# ESP-LED-Schematic.net
KiCad netlist of a schematic drawn in Altium Designer
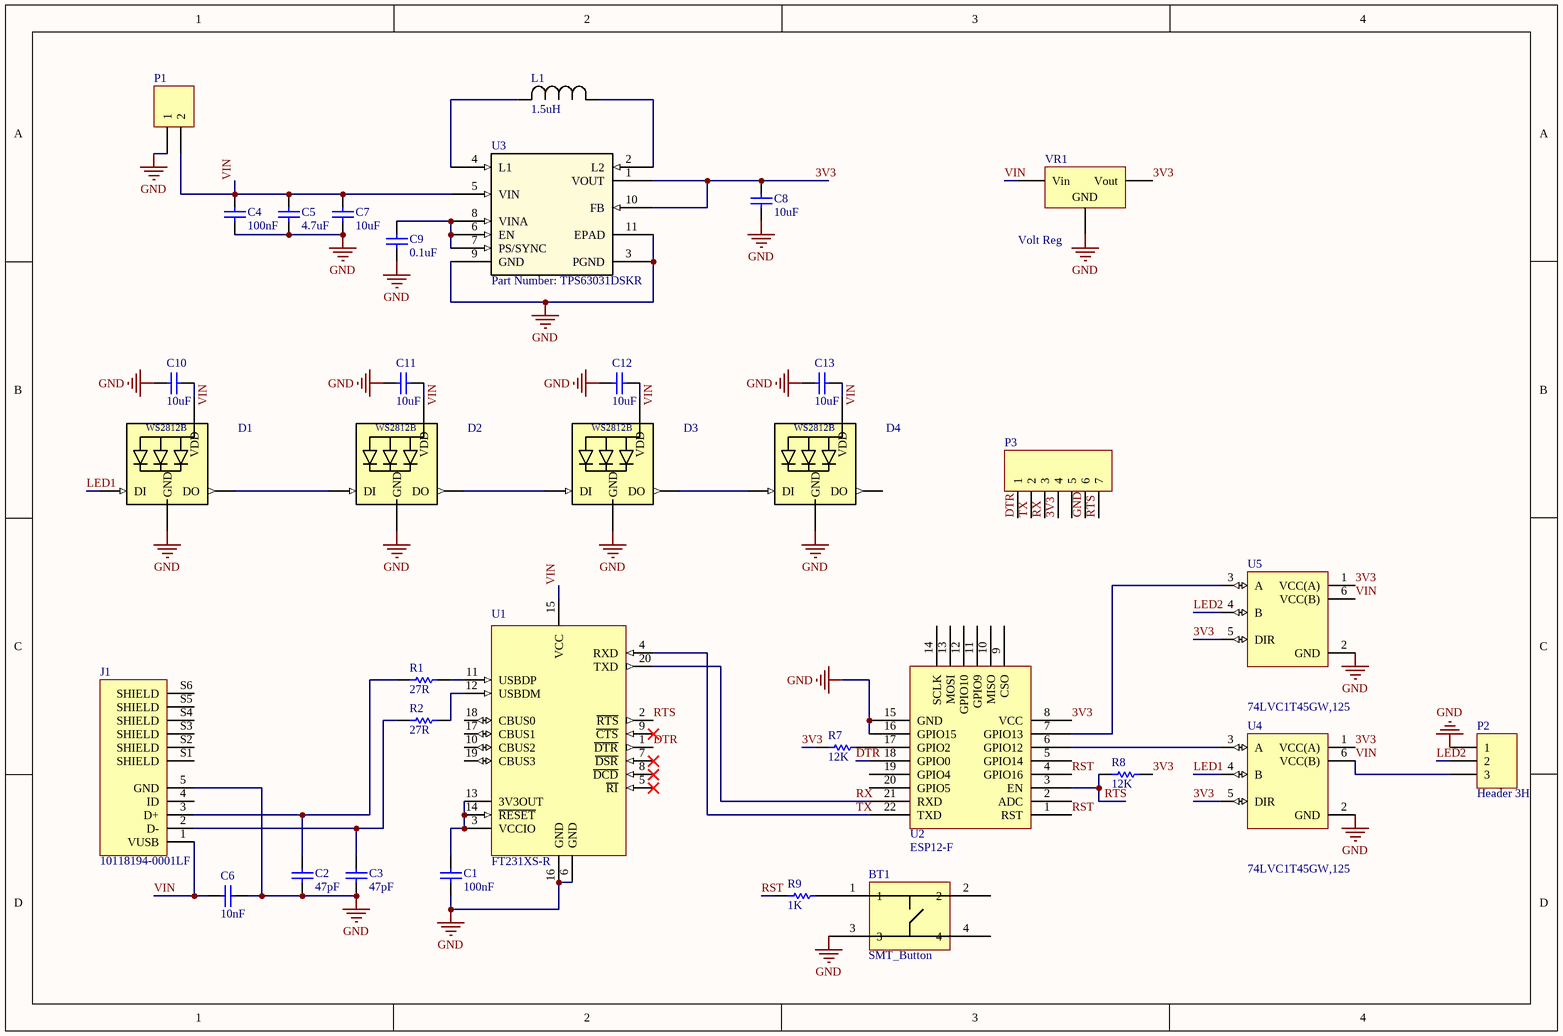
[diagram p0: ESP-LED-Schematic.SchDoc]

(export (version "E")
  (design (tool "Eeschema 10.0.6"))
  (components
    (comp (ref "BT1")
      (value "SMT_Button")
      (footprint "SMT_Button")
      (libsource (lib "CustomComponentsLibrary") (part "SMT_Button"))
    )
    (comp (ref "C1")
      (value "100nF")
      (footprint "6-0805_M")
      (description "Capacitor")
      (fields (field (name "PUBLISHER") "Altium Limited"))
      (libsource (lib "Miscellaneous Devices") (part "Cap"))
    )
    (comp (ref "C2")
      (value "47pF")
      (footprint "6-0805_M")
      (description "Capacitor")
      (fields (field (name "PUBLISHER") "Altium Limited"))
      (libsource (lib "Miscellaneous Devices") (part "Cap"))
    )
    (comp (ref "C3")
      (value "47pF")
      (footprint "6-0805_M")
      (description "Capacitor")
      (fields (field (name "PUBLISHER") "Altium Limited"))
      (libsource (lib "Miscellaneous Devices") (part "Cap"))
    )
    (comp (ref "C4")
      (value "100nF")
      (footprint "6-0805_M")
      (description "Capacitor")
      (fields (field (name "PUBLISHER") "Altium Limited"))
      (libsource (lib "Miscellaneous Devices") (part "Cap"))
    )
    (comp (ref "C5")
      (value "4.7uF")
      (footprint "6-0805_M")
      (description "Capacitor")
      (fields (field (name "PUBLISHER") "Altium Limited"))
      (libsource (lib "Miscellaneous Devices") (part "Cap"))
    )
    (comp (ref "C6")
      (value "10nF")
      (footprint "6-0805_M")
      (description "Capacitor")
      (fields (field (name "PUBLISHER") "Altium Limited"))
      (libsource (lib "Miscellaneous Devices") (part "Cap"))
    )
    (comp (ref "C7")
      (value "10uF")
      (footprint "6-0805_M")
      (description "Capacitor")
      (fields (field (name "PUBLISHER") "Altium Limited"))
      (libsource (lib "Miscellaneous Devices") (part "Cap"))
    )
    (comp (ref "C8")
      (value "10uF")
      (footprint "6-0805_M")
      (description "Capacitor")
      (fields (field (name "PUBLISHER") "Altium Limited"))
      (libsource (lib "Miscellaneous Devices") (part "Cap"))
    )
    (comp (ref "C9")
      (value "0.1uF")
      (footprint "6-0805_M")
      (description "Capacitor")
      (fields (field (name "PUBLISHER") "Altium Limited"))
      (libsource (lib "Miscellaneous Devices") (part "Cap"))
    )
    (comp (ref "C10")
      (value "10uF")
      (footprint "6-0805_M")
      (description "Capacitor")
      (fields (field (name "PUBLISHER") "Altium Limited"))
      (libsource (lib "Miscellaneous Devices") (part "Cap"))
    )
    (comp (ref "C11")
      (value "10uF")
      (footprint "6-0805_M")
      (description "Capacitor")
      (fields (field (name "PUBLISHER") "Altium Limited"))
      (libsource (lib "Miscellaneous Devices") (part "Cap"))
    )
    (comp (ref "C12")
      (value "10uF")
      (footprint "6-0805_M")
      (description "Capacitor")
      (fields (field (name "PUBLISHER") "Altium Limited"))
      (libsource (lib "Miscellaneous Devices") (part "Cap"))
    )
    (comp (ref "C13")
      (value "10uF")
      (footprint "6-0805_M")
      (description "Capacitor")
      (fields (field (name "PUBLISHER") "Altium Limited"))
      (libsource (lib "Miscellaneous Devices") (part "Cap"))
    )
    (comp (ref "D1")
      (value "WS2812B")
      (footprint "*WS2812B_WS2812B(Primary)")
      (description "Intelligent Control Led Integrated Light Source Pack Of 10")
      (fields (field (name "MF") "Worldsemi") (field (name "DIGI-KEY_PART_NUMBER") "1597-1565-ND"))
      (libsource (lib "WS2812B") (part "WS2812B"))
    )
    (comp (ref "D2")
      (value "WS2812B")
      (footprint "*WS2812B_WS2812B(Primary)")
      (description "Intelligent Control Led Integrated Light Source Pack Of 10")
      (fields (field (name "MF") "Worldsemi") (field (name "DIGI-KEY_PART_NUMBER") "1597-1565-ND"))
      (libsource (lib "WS2812B") (part "WS2812B"))
    )
    (comp (ref "D3")
      (value "WS2812B")
      (footprint "*WS2812B_WS2812B(Primary)")
      (description "Intelligent Control Led Integrated Light Source Pack Of 10")
      (fields (field (name "MF") "Worldsemi") (field (name "DIGI-KEY_PART_NUMBER") "1597-1565-ND"))
      (libsource (lib "WS2812B") (part "WS2812B"))
    )
    (comp (ref "D4")
      (value "WS2812B")
      (footprint "*WS2812B_WS2812B(Primary)")
      (description "Intelligent Control Led Integrated Light Source Pack Of 10")
      (fields (field (name "MF") "Worldsemi") (field (name "DIGI-KEY_PART_NUMBER") "1597-1565-ND"))
      (libsource (lib "WS2812B") (part "WS2812B"))
    )
    (comp (ref "J1")
      (value "10118194-0001LF")
      (footprint "*AMPHENOL_10118194-0001LF_10118194-0001LF(Primary)")
      (description "Micro Usb, 2.0 Type b, Rcpt, Smt")
      (fields (field (name "MF") "Amphenol ICC"))
      (libsource (lib "10118194-0001LF") (part "10118194-0001LF"))
    )
    (comp (ref "L1")
      (value "1.5uH")
      (footprint "DFE252012P-1R0M=")
      (description "No Description Available")
      (fields
        (field (name "MANUFACTURER_PART_NUMBER") "DFE252012P-1R5M=P2")
        (field (name "COPYRIGHT") "Copyright (C) 2018 Accelerated Designs. All rights reserved")
      )
      (libsource (lib "2019-06-07_15-16-45") (part "DFE252012P-1R5M="))
    )
    (comp (ref "P1")
      (value "Header 2")
      (footprint "Molex_53048-0210_0")
      (description "Header, 2-Pin")
      (fields (field (name "PUBLISHER") "Altium Limited"))
      (libsource (lib "Miscellaneous Connectors") (part "Header 2"))
    )
    (comp (ref "P2")
      (value "Header 3H")
      (footprint "HDR1X3H")
      (description "Header, 3-Pin, Right Angle")
      (fields (field (name "PUBLISHER") "Altium Limited"))
      (libsource (lib "Miscellaneous Connectors") (part "Header 3H"))
    )
    (comp (ref "P3")
      (value "Header 7")
      (footprint "HDR1X7")
      (description "Header, 7-Pin")
      (fields (field (name "PUBLISHER") "Altium Limited"))
      (libsource (lib "Miscellaneous Connectors") (part "Header 7"))
    )
    (comp (ref "R1")
      (value "27R")
      (footprint "6-0805_M")
      (description "Resistor")
      (fields (field (name "PUBLISHER") "Altium Limited"))
      (libsource (lib "Miscellaneous Devices") (part "Res1"))
    )
    (comp (ref "R2")
      (value "27R")
      (footprint "6-0805_M")
      (description "Resistor")
      (fields (field (name "PUBLISHER") "Altium Limited"))
      (libsource (lib "Miscellaneous Devices") (part "Res1"))
    )
    (comp (ref "R7")
      (value "12K")
      (footprint "6-0805_M")
      (description "Resistor")
      (fields (field (name "PUBLISHER") "Altium Limited"))
      (libsource (lib "Miscellaneous Devices") (part "Res1"))
    )
    (comp (ref "R8")
      (value "12K")
      (footprint "6-0805_M")
      (description "Resistor")
      (fields (field (name "PUBLISHER") "Altium Limited"))
      (libsource (lib "Miscellaneous Devices") (part "Res1"))
    )
    (comp (ref "R9")
      (value "1K")
      (footprint "6-0805_M")
      (description "Resistor")
      (fields (field (name "PUBLISHER") "Altium Limited"))
      (libsource (lib "Miscellaneous Devices") (part "Res1"))
    )
    (comp (ref "U1")
      (value "FT231XS-R")
      (footprint "*SOP63P599X175-20N")
      (description "USB Full Speed to Full Handshake UART with USB Charger Detection")
      (fields (field (name "MF") "FTDI,") (field (name "DIGI-KEY_PART_NUMBER") "768-1129-1-ND"))
      (libsource (lib "FT231XS-R") (part "FT231XS-R"))
    )
    (comp (ref "U2")
      (value "ESP12-F")
      (footprint "ESP12-F")
      (libsource (lib "CustomComponentsLibrary") (part "ESP12-F"))
    )
    (comp (ref "U3")
      (value "Part Number: TPS63031DSKR")
      (footprint "DSK10_2X1P2")
      (description "No Description Available")
      (fields
        (field (name "MANUFACTURER_PART_NUMBER") "TPS63031DSKR")
        (field (name "MANUFACTURER") "Texas Instruments")
        (field (name "COPYRIGHT") "Copyright (C) 2018 Accelerated Designs. All rights reserved")
      )
      (libsource (lib "2019-06-07_05-24-26") (part "TPS63031DSKR"))
    )
    (comp (ref "U4")
      (value "74LVC1T45GW,125")
      (footprint "*SOT65P210X110-6N")
      (description "74LVC_H_1T45 - Dual supply translating transceiver; 3-state")
      (fields (field (name "MF") "Nexperia USA"))
      (libsource (lib "74LVC1T45GW_125") (part "74LVC1T45GW,125"))
    )
    (comp (ref "U5")
      (value "74LVC1T45GW,125")
      (footprint "*SOT65P210X110-6N")
      (description "74LVC_H_1T45 - Dual supply translating transceiver; 3-state")
      (fields (field (name "MF") "Nexperia USA"))
      (libsource (lib "74LVC1T45GW_125") (part "74LVC1T45GW,125"))
    )
    (comp (ref "VR1")
      (value "Volt Reg")
      (footprint "SOT223_N")
      (description "Voltage Regulator")
      (fields (field (name "PUBLISHER") "Altium Limited"))
      (libsource (lib "Miscellaneous Devices") (part "Volt Reg"))
    )
  )
  (nets
    (net (code "1") (name "/3V3") (class "Default")
      (node (ref "C8") (pin "2") (pinfunction "2_2") (pintype "passive"))
      (node (ref "P3") (pin "4") (pinfunction "4_4") (pintype "passive"))
      (node (ref "R7") (pin "1") (pinfunction "1_1") (pintype "passive"))
      (node (ref "R8") (pin "1") (pinfunction "1_1") (pintype "passive"))
      (node (ref "U2") (pin "8") (pinfunction "VCC_8") (pintype "passive"))
      (node (ref "U3") (pin "1") (pinfunction "VOUT_1") (pintype "passive"))
      (node (ref "U3") (pin "10") (pinfunction "FB_10") (pintype "input"))
      (node (ref "U4") (pin "1") (pinfunction "VCC(A)_1") (pintype "power_in"))
      (node (ref "U4") (pin "5") (pinfunction "DIR_5") (pintype "bidirectional"))
      (node (ref "U5") (pin "1") (pinfunction "VCC(A)_1") (pintype "power_in"))
      (node (ref "U5") (pin "5") (pinfunction "DIR_5") (pintype "bidirectional"))
      (node (ref "VR1") (pin "3") (pinfunction "Vout_3") (pintype "passive"))
    )
    (net (code "2") (name "/DTR") (class "Default")
      (node (ref "P3") (pin "1") (pinfunction "1_1") (pintype "passive"))
      (node (ref "U1") (pin "1") (pinfunction "~{DTR}_1") (pintype "output"))
      (node (ref "U2") (pin "18") (pinfunction "GPIO0_18") (pintype "passive"))
    )
    (net (code "3") (name "/LED1") (class "Default")
      (node (ref "D1") (pin "4-DIN") (pinfunction "DI_4-DIN") (pintype "input"))
      (node (ref "U4") (pin "4") (pinfunction "B_4") (pintype "bidirectional"))
    )
    (net (code "4") (name "/LED2") (class "Default")
      (node (ref "P2") (pin "2") (pinfunction "2_2") (pintype "passive"))
      (node (ref "U5") (pin "4") (pinfunction "B_4") (pintype "bidirectional"))
    )
    (net (code "5") (name "/RST") (class "Default")
      (node (ref "R9") (pin "2") (pinfunction "2_2") (pintype "passive"))
      (node (ref "U2") (pin "1") (pinfunction "RST_1") (pintype "passive"))
      (node (ref "U2") (pin "4") (pinfunction "GPIO16_4") (pintype "passive"))
    )
    (net (code "6") (name "/RTS") (class "Default")
      (node (ref "P3") (pin "7") (pinfunction "7_7") (pintype "passive"))
      (node (ref "R8") (pin "2") (pinfunction "2_2") (pintype "passive"))
      (node (ref "U1") (pin "2") (pinfunction "~{RTS}_2") (pintype "output"))
      (node (ref "U2") (pin "3") (pinfunction "EN_3") (pintype "passive"))
    )
    (net (code "7") (name "/RX") (class "Default")
      (node (ref "P3") (pin "3") (pinfunction "3_3") (pintype "passive"))
      (node (ref "U1") (pin "20") (pinfunction "TXD_20") (pintype "output"))
      (node (ref "U2") (pin "21") (pinfunction "RXD_21") (pintype "passive"))
    )
    (net (code "8") (name "/TX") (class "Default")
      (node (ref "P3") (pin "2") (pinfunction "2_2") (pintype "passive"))
      (node (ref "U1") (pin "4") (pinfunction "RXD_4") (pintype "input"))
      (node (ref "U2") (pin "22") (pinfunction "TXD_22") (pintype "passive"))
    )
    (net (code "9") (name "/VIN") (class "Default")
      (node (ref "C10") (pin "1") (pinfunction "1_1") (pintype "passive"))
      (node (ref "C11") (pin "1") (pinfunction "1_1") (pintype "passive"))
      (node (ref "C12") (pin "1") (pinfunction "1_1") (pintype "passive"))
      (node (ref "C13") (pin "1") (pinfunction "1_1") (pintype "passive"))
      (node (ref "C4") (pin "1") (pinfunction "1_1") (pintype "passive"))
      (node (ref "C5") (pin "1") (pinfunction "1_1") (pintype "passive"))
      (node (ref "C6") (pin "2") (pinfunction "2_2") (pintype "passive"))
      (node (ref "C7") (pin "2") (pinfunction "2_2") (pintype "passive"))
      (node (ref "D1") (pin "1-VDD") (pinfunction "VDD_1-VDD") (pintype "power_in"))
      (node (ref "D2") (pin "1-VDD") (pinfunction "VDD_1-VDD") (pintype "power_in"))
      (node (ref "D3") (pin "1-VDD") (pinfunction "VDD_1-VDD") (pintype "power_in"))
      (node (ref "D4") (pin "1-VDD") (pinfunction "VDD_1-VDD") (pintype "power_in"))
      (node (ref "J1") (pin "1") (pinfunction "VUSB_1") (pintype "passive"))
      (node (ref "P1") (pin "2") (pinfunction "2_2") (pintype "passive"))
      (node (ref "P2") (pin "3") (pinfunction "3_3") (pintype "passive"))
      (node (ref "U1") (pin "15") (pinfunction "VCC_15") (pintype "power_in"))
      (node (ref "U3") (pin "5") (pinfunction "VIN_5") (pintype "input"))
      (node (ref "U4") (pin "6") (pinfunction "VCC(B)_6") (pintype "power_in"))
      (node (ref "U5") (pin "6") (pinfunction "VCC(B)_6") (pintype "power_in"))
      (node (ref "VR1") (pin "1") (pinfunction "Vin_1") (pintype "passive"))
    )
    (net (code "10") (name "GND") (class "Default")
      (node (ref "BT1") (pin "3") (pinfunction "3_3") (pintype "passive"))
      (node (ref "C1") (pin "1") (pinfunction "1_1") (pintype "passive"))
      (node (ref "C10") (pin "2") (pinfunction "2_2") (pintype "passive"))
      (node (ref "C11") (pin "2") (pinfunction "2_2") (pintype "passive"))
      (node (ref "C12") (pin "2") (pinfunction "2_2") (pintype "passive"))
      (node (ref "C13") (pin "2") (pinfunction "2_2") (pintype "passive"))
      (node (ref "C2") (pin "2") (pinfunction "2_2") (pintype "passive"))
      (node (ref "C3") (pin "2") (pinfunction "2_2") (pintype "passive"))
      (node (ref "C4") (pin "2") (pinfunction "2_2") (pintype "passive"))
      (node (ref "C5") (pin "2") (pinfunction "2_2") (pintype "passive"))
      (node (ref "C6") (pin "1") (pinfunction "1_1") (pintype "passive"))
      (node (ref "C7") (pin "1") (pinfunction "1_1") (pintype "passive"))
      (node (ref "C8") (pin "1") (pinfunction "1_1") (pintype "passive"))
      (node (ref "C9") (pin "1") (pinfunction "1_1") (pintype "passive"))
      (node (ref "D1") (pin "3-GND") (pinfunction "GND_3-GND") (pintype "power_in"))
      (node (ref "D2") (pin "3-GND") (pinfunction "GND_3-GND") (pintype "power_in"))
      (node (ref "D3") (pin "3-GND") (pinfunction "GND_3-GND") (pintype "power_in"))
      (node (ref "D4") (pin "3-GND") (pinfunction "GND_3-GND") (pintype "power_in"))
      (node (ref "J1") (pin "5") (pinfunction "GND_5") (pintype "passive"))
      (node (ref "P1") (pin "1") (pinfunction "1_1") (pintype "passive"))
      (node (ref "P2") (pin "1") (pinfunction "1_1") (pintype "passive"))
      (node (ref "P3") (pin "6") (pinfunction "6_6") (pintype "passive"))
      (node (ref "U1") (pin "16") (pinfunction "GND_16") (pintype "power_in"))
      (node (ref "U1") (pin "6") (pinfunction "GND_6") (pintype "power_in"))
      (node (ref "U2") (pin "15") (pinfunction "GND_15") (pintype "passive"))
      (node (ref "U2") (pin "16") (pinfunction "GPIO15_16") (pintype "passive"))
      (node (ref "U3") (pin "11") (pinfunction "EPAD_11") (pintype "passive"))
      (node (ref "U3") (pin "3") (pinfunction "PGND_3") (pintype "power_in"))
      (node (ref "U3") (pin "9") (pinfunction "GND_9") (pintype "power_in"))
      (node (ref "U4") (pin "2") (pinfunction "GND_2") (pintype "power_in"))
      (node (ref "U5") (pin "2") (pinfunction "GND_2") (pintype "power_in"))
      (node (ref "VR1") (pin "2") (pinfunction "GND_2") (pintype "passive"))
    )
    (net (code "11") (name "Net-(BT1-Pad1)") (class "Default")
      (node (ref "BT1") (pin "1") (pinfunction "1_1") (pintype "passive"))
      (node (ref "R9") (pin "1") (pinfunction "1_1") (pintype "passive"))
    )
    (net (code "12") (name "Net-(D1-DO)") (class "Default")
      (node (ref "D1") (pin "2-DOUT") (pinfunction "DO_2-DOUT") (pintype "output"))
      (node (ref "D2") (pin "4-DIN") (pinfunction "DI_4-DIN") (pintype "input"))
    )
    (net (code "13") (name "Net-(D2-DO)") (class "Default")
      (node (ref "D2") (pin "2-DOUT") (pinfunction "DO_2-DOUT") (pintype "output"))
      (node (ref "D3") (pin "4-DIN") (pinfunction "DI_4-DIN") (pintype "input"))
    )
    (net (code "14") (name "Net-(D3-DO)") (class "Default")
      (node (ref "D3") (pin "2-DOUT") (pinfunction "DO_2-DOUT") (pintype "output"))
      (node (ref "D4") (pin "4-DIN") (pinfunction "DI_4-DIN") (pintype "input"))
    )
    (net (code "15") (name "Net-(J1-D+)") (class "Default")
      (node (ref "C2") (pin "1") (pinfunction "1_1") (pintype "passive"))
      (node (ref "J1") (pin "3") (pinfunction "D+_3") (pintype "passive"))
      (node (ref "R1") (pin "1") (pinfunction "1_1") (pintype "passive"))
    )
    (net (code "16") (name "Net-(J1-D-)") (class "Default")
      (node (ref "C3") (pin "1") (pinfunction "1_1") (pintype "passive"))
      (node (ref "J1") (pin "2") (pinfunction "D-_2") (pintype "passive"))
      (node (ref "R2") (pin "1") (pinfunction "1_1") (pintype "passive"))
    )
    (net (code "17") (name "Net-(U1-3V3OUT)") (class "Default")
      (node (ref "C1") (pin "2") (pinfunction "2_2") (pintype "passive"))
      (node (ref "U1") (pin "13") (pinfunction "3V3OUT_13") (pintype "power_in"))
      (node (ref "U1") (pin "14") (pinfunction "~{RESET}_14") (pintype "input"))
      (node (ref "U1") (pin "3") (pinfunction "VCCIO_3") (pintype "power_in"))
    )
    (net (code "18") (name "Net-(U1-USBDM)") (class "Default")
      (node (ref "R2") (pin "2") (pinfunction "2_2") (pintype "passive"))
      (node (ref "U1") (pin "12") (pinfunction "USBDM_12") (pintype "input"))
    )
    (net (code "19") (name "Net-(U1-USBDP)") (class "Default")
      (node (ref "R1") (pin "2") (pinfunction "2_2") (pintype "passive"))
      (node (ref "U1") (pin "11") (pinfunction "USBDP_11") (pintype "input"))
    )
    (net (code "20") (name "Net-(U2-GPIO2)") (class "Default")
      (node (ref "R7") (pin "2") (pinfunction "2_2") (pintype "passive"))
      (node (ref "U2") (pin "17") (pinfunction "GPIO2_17") (pintype "passive"))
    )
    (net (code "21") (name "Net-(U2-GPIO12)") (class "Default")
      (node (ref "U2") (pin "6") (pinfunction "GPIO12_6") (pintype "passive"))
      (node (ref "U4") (pin "3") (pinfunction "A_3") (pintype "bidirectional"))
    )
    (net (code "22") (name "Net-(U2-GPIO13)") (class "Default")
      (node (ref "U2") (pin "7") (pinfunction "GPIO13_7") (pintype "passive"))
      (node (ref "U5") (pin "3") (pinfunction "A_3") (pintype "bidirectional"))
    )
    (net (code "23") (name "Net-(U3-EN)") (class "Default")
      (node (ref "C9") (pin "2") (pinfunction "2_2") (pintype "passive"))
      (node (ref "U3") (pin "6") (pinfunction "EN_6") (pintype "input"))
      (node (ref "U3") (pin "7") (pinfunction "PS/SYNC_7") (pintype "input"))
      (node (ref "U3") (pin "8") (pinfunction "VINA_8") (pintype "input"))
    )
    (net (code "24") (name "Net-(U3-L1)") (class "Default")
      (node (ref "L1") (pin "2") (pinfunction "2_2") (pintype "passive"))
      (node (ref "U3") (pin "4") (pinfunction "L1_4") (pintype "input"))
    )
    (net (code "25") (name "Net-(U3-L2)") (class "Default")
      (node (ref "L1") (pin "1") (pinfunction "1_1") (pintype "passive"))
      (node (ref "U3") (pin "2") (pinfunction "L2_2") (pintype "input"))
    )
    (net (code "26") (name "unconnected-(BT1-Pad2)") (class "Default")
      (node (ref "BT1") (pin "2") (pinfunction "2_2") (pintype "passive"))
    )
    (net (code "27") (name "unconnected-(BT1-Pad4)") (class "Default")
      (node (ref "BT1") (pin "4") (pinfunction "4_4") (pintype "passive"))
    )
    (net (code "28") (name "unconnected-(D4-DO-Pad2-DOUT)") (class "Default")
      (node (ref "D4") (pin "2-DOUT") (pinfunction "DO_2-DOUT") (pintype "output"))
    )
    (net (code "29") (name "unconnected-(J1-ID-Pad4)") (class "Default")
      (node (ref "J1") (pin "4") (pinfunction "ID_4") (pintype "passive"))
    )
    (net (code "30") (name "unconnected-(J1-SHIELD-PadS1)") (class "Default")
      (node (ref "J1") (pin "S1") (pinfunction "SHIELD_S1") (pintype "passive"))
    )
    (net (code "31") (name "unconnected-(J1-SHIELD-PadS2)") (class "Default")
      (node (ref "J1") (pin "S2") (pinfunction "SHIELD_S2") (pintype "passive"))
    )
    (net (code "32") (name "unconnected-(J1-SHIELD-PadS3)") (class "Default")
      (node (ref "J1") (pin "S3") (pinfunction "SHIELD_S3") (pintype "passive"))
    )
    (net (code "33") (name "unconnected-(J1-SHIELD-PadS4)") (class "Default")
      (node (ref "J1") (pin "S4") (pinfunction "SHIELD_S4") (pintype "passive"))
    )
    (net (code "34") (name "unconnected-(J1-SHIELD-PadS5)") (class "Default")
      (node (ref "J1") (pin "S5") (pinfunction "SHIELD_S5") (pintype "passive"))
    )
    (net (code "35") (name "unconnected-(J1-SHIELD-PadS6)") (class "Default")
      (node (ref "J1") (pin "S6") (pinfunction "SHIELD_S6") (pintype "passive"))
    )
    (net (code "36") (name "unconnected-(P3-Pad5)") (class "Default")
      (node (ref "P3") (pin "5") (pinfunction "5_5") (pintype "passive"))
    )
    (net (code "37") (name "unconnected-(U1-CBUS0-Pad18)") (class "Default")
      (node (ref "U1") (pin "18") (pinfunction "CBUS0_18") (pintype "bidirectional"))
    )
    (net (code "38") (name "unconnected-(U1-CBUS1-Pad17)") (class "Default")
      (node (ref "U1") (pin "17") (pinfunction "CBUS1_17") (pintype "bidirectional"))
    )
    (net (code "39") (name "unconnected-(U1-CBUS2-Pad10)") (class "Default")
      (node (ref "U1") (pin "10") (pinfunction "CBUS2_10") (pintype "bidirectional"))
    )
    (net (code "40") (name "unconnected-(U1-CBUS3-Pad19)") (class "Default")
      (node (ref "U1") (pin "19") (pinfunction "CBUS3_19") (pintype "bidirectional"))
    )
    (net (code "41") (name "unconnected-(U1-~{CTS}-Pad9)") (class "Default")
      (node (ref "U1") (pin "9") (pinfunction "~{CTS}_9") (pintype "input+no_connect"))
    )
    (net (code "42") (name "unconnected-(U1-~{DCD}-Pad8)") (class "Default")
      (node (ref "U1") (pin "8") (pinfunction "~{DCD}_8") (pintype "input+no_connect"))
    )
    (net (code "43") (name "unconnected-(U1-~{DSR}-Pad7)") (class "Default")
      (node (ref "U1") (pin "7") (pinfunction "~{DSR}_7") (pintype "input+no_connect"))
    )
    (net (code "44") (name "unconnected-(U1-~{RI}-Pad5)") (class "Default")
      (node (ref "U1") (pin "5") (pinfunction "~{RI}_5") (pintype "input+no_connect"))
    )
    (net (code "45") (name "unconnected-(U2-ADC-Pad2)") (class "Default")
      (node (ref "U2") (pin "2") (pinfunction "ADC_2") (pintype "passive"))
    )
    (net (code "46") (name "unconnected-(U2-CSO-Pad9)") (class "Default")
      (node (ref "U2") (pin "9") (pinfunction "CSO_9") (pintype "passive"))
    )
    (net (code "47") (name "unconnected-(U2-GPIO4-Pad19)") (class "Default")
      (node (ref "U2") (pin "19") (pinfunction "GPIO4_19") (pintype "passive"))
    )
    (net (code "48") (name "unconnected-(U2-GPIO5-Pad20)") (class "Default")
      (node (ref "U2") (pin "20") (pinfunction "GPIO5_20") (pintype "passive"))
    )
    (net (code "49") (name "unconnected-(U2-GPIO9-Pad11)") (class "Default")
      (node (ref "U2") (pin "11") (pinfunction "GPIO9_11") (pintype "passive"))
    )
    (net (code "50") (name "unconnected-(U2-GPIO10-Pad12)") (class "Default")
      (node (ref "U2") (pin "12") (pinfunction "GPIO10_12") (pintype "passive"))
    )
    (net (code "51") (name "unconnected-(U2-GPIO14-Pad5)") (class "Default")
      (node (ref "U2") (pin "5") (pinfunction "GPIO14_5") (pintype "passive"))
    )
    (net (code "52") (name "unconnected-(U2-MISO-Pad10)") (class "Default")
      (node (ref "U2") (pin "10") (pinfunction "MISO_10") (pintype "passive"))
    )
    (net (code "53") (name "unconnected-(U2-MOSI-Pad13)") (class "Default")
      (node (ref "U2") (pin "13") (pinfunction "MOSI_13") (pintype "passive"))
    )
    (net (code "54") (name "unconnected-(U2-SCLK-Pad14)") (class "Default")
      (node (ref "U2") (pin "14") (pinfunction "SCLK_14") (pintype "passive"))
    )
  )
)
